# Arduino_Leonardo-REV3b.net
KiCad netlist of a schematic drawn in EAGLE
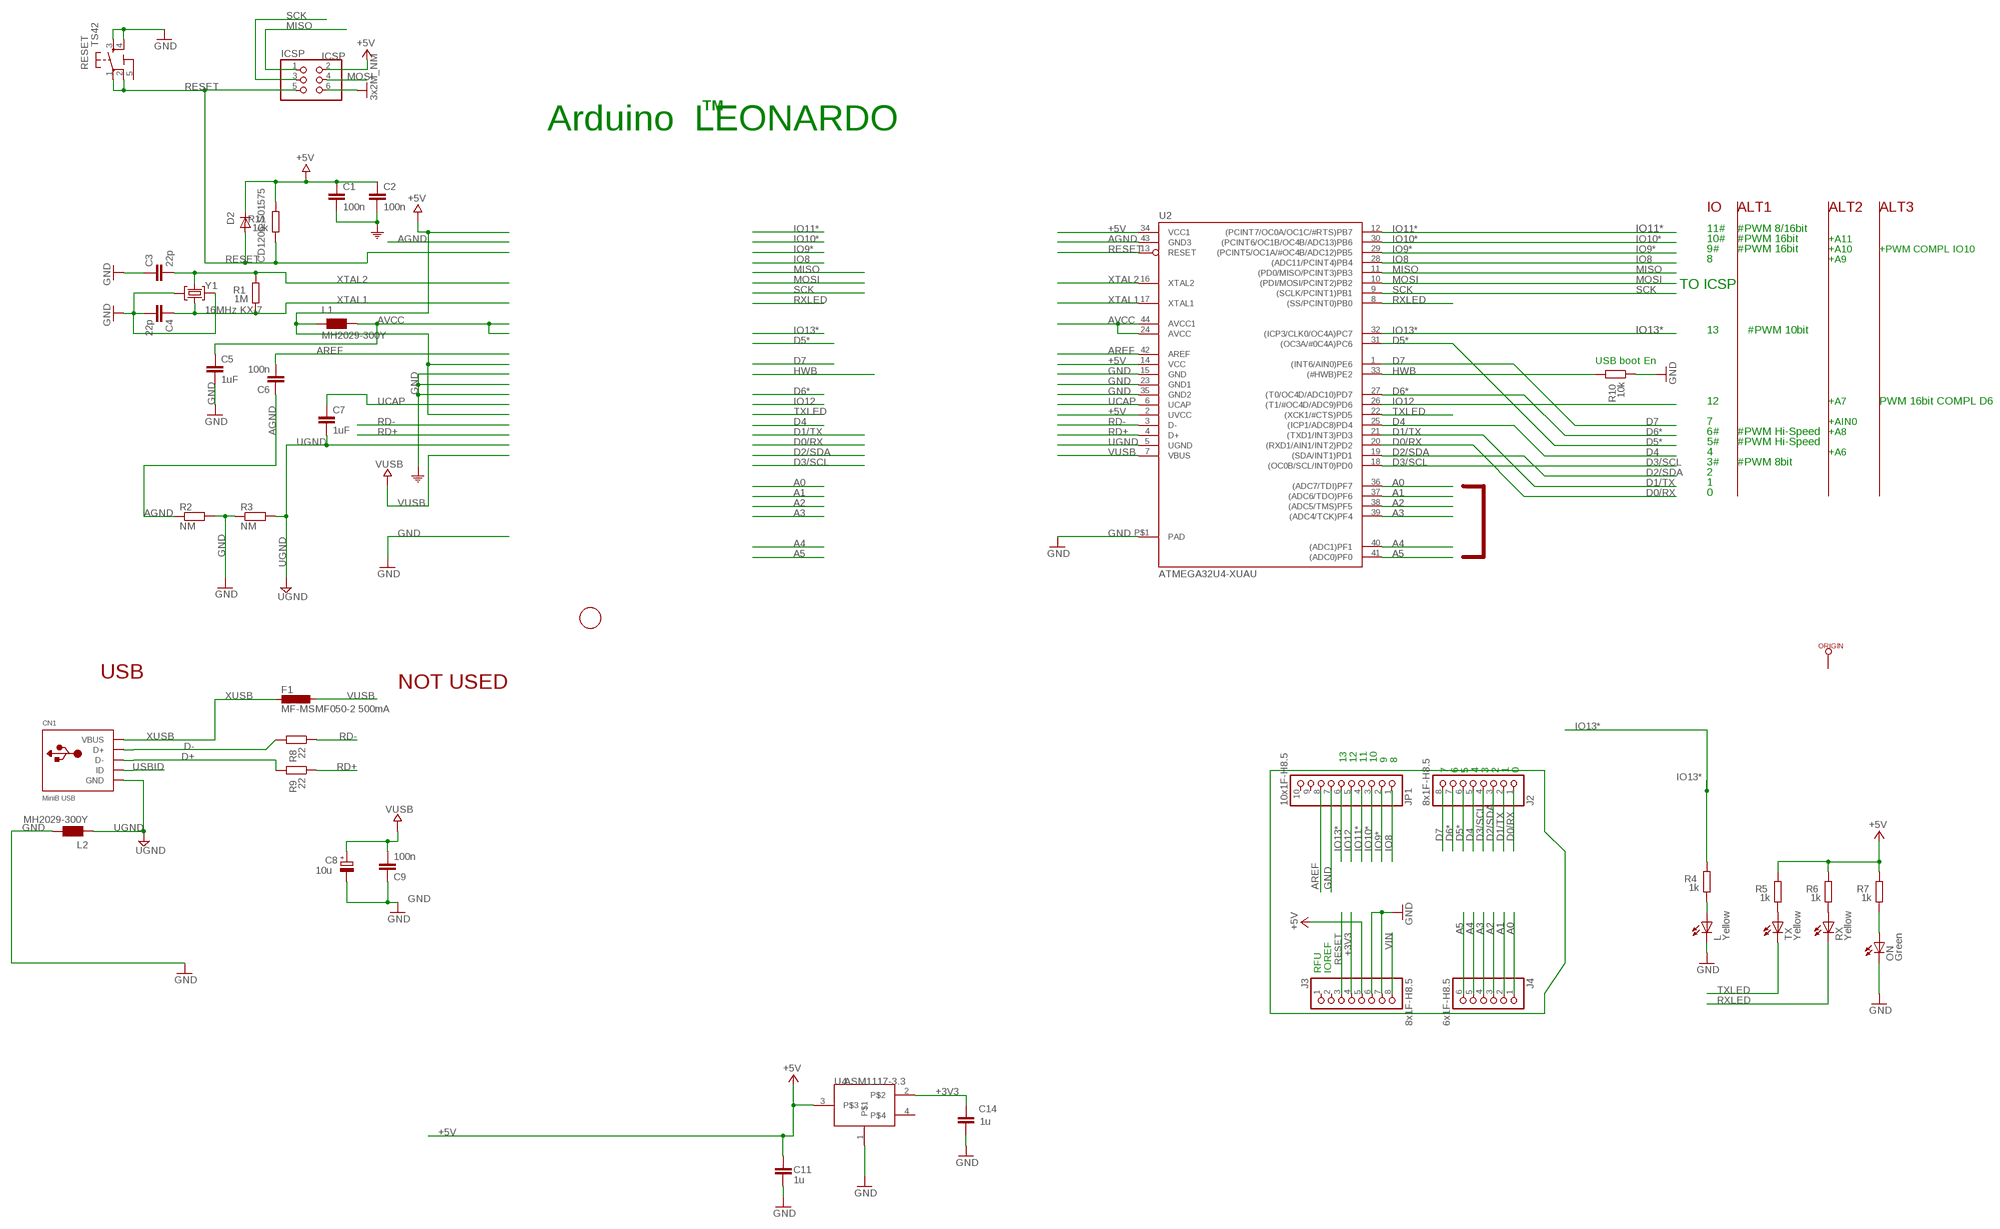
[diagram p0: schematic, sheet 1]

(export (version "E")
  (design (tool "Eeschema 10.0.6"))
  (components
    (comp (ref "C1")
      (value "100n")
      (footprint "eagle-import:C0805")
      (libsource (lib "eagle-import") (part "C-EUC0805"))
    )
    (comp (ref "C2")
      (value "100n")
      (footprint "eagle-import:C0805")
      (libsource (lib "eagle-import") (part "C-EUC0805"))
    )
    (comp (ref "C3")
      (value "22p")
      (footprint "eagle-import:C0805")
      (libsource (lib "eagle-import") (part "C-EUC0805"))
    )
    (comp (ref "C4")
      (value "22p")
      (footprint "eagle-import:C0805")
      (libsource (lib "eagle-import") (part "C-EUC0805"))
    )
    (comp (ref "C5")
      (value "1uF")
      (footprint "eagle-import:C0805")
      (libsource (lib "eagle-import") (part "C-EUC0805"))
    )
    (comp (ref "C6")
      (value "100n")
      (footprint "eagle-import:C0805")
      (libsource (lib "eagle-import") (part "C-EUC0805"))
    )
    (comp (ref "C7")
      (value "1uF")
      (footprint "eagle-import:C0805")
      (libsource (lib "eagle-import") (part "C-EUC0805"))
    )
    (comp (ref "C8")
      (value "10u")
      (footprint "eagle-import:SMC_B")
      (libsource (lib "eagle-import") (part "CPOL-EUSMCB"))
    )
    (comp (ref "C9")
      (value "100n")
      (footprint "eagle-import:C0805")
      (libsource (lib "eagle-import") (part "C-EUC0805"))
    )
    (comp (ref "C11")
      (value "1u")
      (footprint "eagle-import:C0805")
      (libsource (lib "eagle-import") (part "C-EUC0805"))
    )
    (comp (ref "C14")
      (value "1u")
      (footprint "eagle-import:C0805")
      (libsource (lib "eagle-import") (part "C-EUC0805"))
    )
    (comp (ref "CN1")
      (value "MiniB USB")
      (footprint "eagle-import:USB-MINIB")
      (libsource (lib "eagle-import") (part "USBMINIB"))
    )
    (comp (ref "D2")
      (value "CD1206-S01575")
      (footprint "eagle-import:MINIMELF")
      (libsource (lib "eagle-import") (part "DIODE-MINIMELF"))
    )
    (comp (ref "F1")
      (value "MF-MSMF050-2 500mA")
      (footprint "eagle-import:L1812")
      (libsource (lib "eagle-import") (part "L-EUL1812"))
    )
    (comp (ref "FID1")
      (value "FIDUCIALMOUNT")
      (footprint "eagle-import:FIDUCIA-MOUNT")
      (libsource (lib "eagle-import") (part "FIDUCIALMOUNT"))
    )
    (comp (ref "ICSP")
      (value "ICSP")
      (footprint "eagle-import:2X03")
      (libsource (lib "eagle-import") (part "PINHD-2X3"))
    )
    (comp (ref "J2")
      (value "8x1F-H8.5")
      (footprint "eagle-import:1X08")
      (libsource (lib "eagle-import") (part "PINHD-1X8"))
    )
    (comp (ref "J3")
      (value "8x1F-H8.5")
      (footprint "eagle-import:1X08")
      (libsource (lib "eagle-import") (part "PINHD-1X8"))
    )
    (comp (ref "J4")
      (value "6x1F-H8.5")
      (footprint "eagle-import:1X06")
      (libsource (lib "eagle-import") (part "PINHD-1X6"))
    )
    (comp (ref "JP1")
      (value "10x1F-H8.5")
      (footprint "eagle-import:1X10")
      (libsource (lib "eagle-import") (part "PINHD-1X10"))
    )
    (comp (ref "L")
      (value "Yellow")
      (footprint "eagle-import:CHIPLED_0805")
      (libsource (lib "eagle-import") (part "LEDCHIPLED_0805"))
    )
    (comp (ref "L1")
      (value "MH2029-300Y")
      (footprint "eagle-import:0805")
      (libsource (lib "eagle-import") (part "WE-CBF_0805"))
    )
    (comp (ref "L2")
      (value "MH2029-300Y")
      (footprint "eagle-import:0805")
      (libsource (lib "eagle-import") (part "WE-CBF_0805"))
    )
    (comp (ref "ON")
      (value "Green")
      (footprint "eagle-import:CHIPLED_0805")
      (libsource (lib "eagle-import") (part "LEDCHIPLED_0805"))
    )
    (comp (ref "ORIGIN")
      (value "TP_SP")
      (footprint "eagle-import:TP-SP")
      (libsource (lib "eagle-import") (part "TP_SP"))
    )
    (comp (ref "R1")
      (value "1M")
      (footprint "eagle-import:R0805")
      (libsource (lib "eagle-import") (part "R-EU_R0805"))
    )
    (comp (ref "R2")
      (value "NM")
      (footprint "eagle-import:R0805")
      (libsource (lib "eagle-import") (part "R-EU_R0805"))
    )
    (comp (ref "R3")
      (value "NM")
      (footprint "eagle-import:R0805")
      (libsource (lib "eagle-import") (part "R-EU_R0805"))
    )
    (comp (ref "R4")
      (value "1k")
      (footprint "eagle-import:R0805")
      (libsource (lib "eagle-import") (part "R-EU_R0805"))
    )
    (comp (ref "R5")
      (value "1k")
      (footprint "eagle-import:R0805")
      (libsource (lib "eagle-import") (part "R-EU_R0805"))
    )
    (comp (ref "R6")
      (value "1k")
      (footprint "eagle-import:R0805")
      (libsource (lib "eagle-import") (part "R-EU_R0805"))
    )
    (comp (ref "R7")
      (value "1k")
      (footprint "eagle-import:R0805")
      (libsource (lib "eagle-import") (part "R-EU_R0805"))
    )
    (comp (ref "R8")
      (value "22")
      (footprint "eagle-import:R0805")
      (libsource (lib "eagle-import") (part "R-EU_R0805"))
    )
    (comp (ref "R9")
      (value "22")
      (footprint "eagle-import:R0805")
      (libsource (lib "eagle-import") (part "R-EU_R0805"))
    )
    (comp (ref "R10")
      (value "10k")
      (footprint "eagle-import:R0805")
      (libsource (lib "eagle-import") (part "R-EU_R0805"))
    )
    (comp (ref "R11")
      (value "10k")
      (footprint "eagle-import:R0805")
      (libsource (lib "eagle-import") (part "R-EU_R0805"))
    )
    (comp (ref "RESET")
      (value "TS42")
      (footprint "eagle-import:TS42")
      (libsource (lib "eagle-import") (part "TS42"))
    )
    (comp (ref "RX")
      (value "Yellow")
      (footprint "eagle-import:CHIPLED_0805")
      (libsource (lib "eagle-import") (part "LEDCHIPLED_0805"))
    )
    (comp (ref "TX")
      (value "Yellow")
      (footprint "eagle-import:CHIPLED_0805")
      (libsource (lib "eagle-import") (part "LEDCHIPLED_0805"))
    )
    (comp (ref "U2")
      (value "ATMEGA32U4-XUAU")
      (footprint "eagle-import:TQFP44-PAD")
      (libsource (lib "eagle-import") (part "ATMEGA32U4-XUAU"))
    )
    (comp (ref "U4")
      (value "ASM1117-3.3")
      (footprint "eagle-import:SOT223")
      (libsource (lib "eagle-import") (part "ASM1117-3.3"))
    )
    (comp (ref "Y1")
      (value "16MHz KX-7")
      (footprint "eagle-import:CRYSTAL-3.2-2.5")
      (libsource (lib "eagle-import") (part "CRYSTAL-3.2-2.5"))
    )
  )
  (nets
    (net (code "1") (name "+5V") (class "Default")
      (node (ref "C1") (pin "1") (pinfunction "1_1") (pintype "passive"))
      (node (ref "C11") (pin "2") (pinfunction "2_2") (pintype "passive"))
      (node (ref "C2") (pin "1") (pinfunction "1_1") (pintype "passive"))
      (node (ref "D2") (pin "C") (pinfunction "C_C") (pintype "passive"))
      (node (ref "ICSP") (pin "2") (pinfunction "2_2") (pintype "passive"))
      (node (ref "J3") (pin "5") (pinfunction "5_5") (pintype "passive"))
      (node (ref "L1") (pin "1") (pinfunction "1_1") (pintype "passive"))
      (node (ref "R11") (pin "2") (pinfunction "2_2") (pintype "passive"))
      (node (ref "R5") (pin "2") (pinfunction "2_2") (pintype "passive"))
      (node (ref "R6") (pin "2") (pinfunction "2_2") (pintype "passive"))
      (node (ref "R7") (pin "2") (pinfunction "2_2") (pintype "passive"))
      (node (ref "U2") (pin "14") (pinfunction "VCC_14") (pintype "power_in"))
      (node (ref "U2") (pin "2") (pinfunction "UVCC_2") (pintype "power_in"))
      (node (ref "U2") (pin "34") (pinfunction "VCC1_34") (pintype "power_in"))
      (node (ref "U4") (pin "3") (pinfunction "P$3_3") (pintype "bidirectional"))
    )
    (net (code "2") (name "/+3V3") (class "Default")
      (node (ref "C14") (pin "2") (pinfunction "2_2") (pintype "passive"))
      (node (ref "J3") (pin "4") (pinfunction "4_4") (pintype "passive"))
      (node (ref "U4") (pin "2") (pinfunction "P$2_2") (pintype "bidirectional"))
    )
    (net (code "3") (name "/5-GND") (class "Default")
      (node (ref "RESET") (pin "5") (pinfunction "5-GND_5") (pintype "power_in"))
    )
    (net (code "4") (name "/A0") (class "Default")
      (node (ref "J4") (pin "1") (pinfunction "1_1") (pintype "passive"))
      (node (ref "U2") (pin "36") (pinfunction "(ADC7/TDI)PF7_36") (pintype "bidirectional"))
    )
    (net (code "5") (name "/A1") (class "Default")
      (node (ref "J4") (pin "2") (pinfunction "2_2") (pintype "passive"))
      (node (ref "U2") (pin "37") (pinfunction "(ADC6/TDO)PF6_37") (pintype "bidirectional"))
    )
    (net (code "6") (name "/A2") (class "Default")
      (node (ref "J4") (pin "3") (pinfunction "3_3") (pintype "passive"))
      (node (ref "U2") (pin "38") (pinfunction "(ADC5/TMS)PF5_38") (pintype "bidirectional"))
    )
    (net (code "7") (name "/A3") (class "Default")
      (node (ref "J4") (pin "4") (pinfunction "4_4") (pintype "passive"))
      (node (ref "U2") (pin "39") (pinfunction "(ADC4/TCK)PF4_39") (pintype "bidirectional"))
    )
    (net (code "8") (name "/A4") (class "Default")
      (node (ref "J4") (pin "5") (pinfunction "5_5") (pintype "passive"))
      (node (ref "U2") (pin "40") (pinfunction "(ADC1)PF1_40") (pintype "bidirectional"))
    )
    (net (code "9") (name "/A5") (class "Default")
      (node (ref "J4") (pin "6") (pinfunction "6_6") (pintype "passive"))
      (node (ref "U2") (pin "41") (pinfunction "(ADC0)PF0_41") (pintype "bidirectional"))
    )
    (net (code "10") (name "/AGND") (class "Default")
      (node (ref "C6") (pin "1") (pinfunction "1_1") (pintype "passive"))
      (node (ref "R2") (pin "1") (pinfunction "1_1") (pintype "passive"))
      (node (ref "U2") (pin "43") (pinfunction "GND3_43") (pintype "power_in"))
    )
    (net (code "11") (name "/AREF") (class "Default")
      (node (ref "C6") (pin "2") (pinfunction "2_2") (pintype "passive"))
      (node (ref "JP1") (pin "8") (pinfunction "8_8") (pintype "passive"))
      (node (ref "U2") (pin "42") (pinfunction "AREF_42") (pintype "power_in"))
    )
    (net (code "12") (name "/AVCC") (class "Default")
      (node (ref "C5") (pin "1") (pinfunction "1_1") (pintype "passive"))
      (node (ref "L1") (pin "2") (pinfunction "2_2") (pintype "passive"))
      (node (ref "U2") (pin "24") (pinfunction "AVCC_24") (pintype "power_in"))
      (node (ref "U2") (pin "44") (pinfunction "AVCC1_44") (pintype "power_in"))
    )
    (net (code "13") (name "/D+") (class "Default")
      (node (ref "CN1") (pin "D-") (pinfunction "D-_D-") (pintype "bidirectional"))
      (node (ref "R9") (pin "2") (pinfunction "2_2") (pintype "passive"))
    )
    (net (code "14") (name "/D-") (class "Default")
      (node (ref "CN1") (pin "D+") (pinfunction "D+_D+") (pintype "bidirectional"))
      (node (ref "R8") (pin "2") (pinfunction "2_2") (pintype "passive"))
    )
    (net (code "15") (name "/D0{slash}RX") (class "Default")
      (node (ref "J2") (pin "1") (pinfunction "1_1") (pintype "passive"))
      (node (ref "U2") (pin "20") (pinfunction "(RXD1/AIN1/INT2)PD2_20") (pintype "bidirectional"))
    )
    (net (code "16") (name "/D1{slash}TX") (class "Default")
      (node (ref "J2") (pin "2") (pinfunction "2_2") (pintype "passive"))
      (node (ref "U2") (pin "21") (pinfunction "(TXD1/INT3)PD3_21") (pintype "bidirectional"))
    )
    (net (code "17") (name "/D2{slash}SDA") (class "Default")
      (node (ref "J2") (pin "3") (pinfunction "3_3") (pintype "passive"))
      (node (ref "U2") (pin "19") (pinfunction "(SDA/INT1)PD1_19") (pintype "bidirectional"))
    )
    (net (code "18") (name "/D3{slash}SCL") (class "Default")
      (node (ref "J2") (pin "4") (pinfunction "4_4") (pintype "passive"))
      (node (ref "U2") (pin "18") (pinfunction "(OC0B/SCL/INT0)PD0_18") (pintype "bidirectional"))
    )
    (net (code "19") (name "/D4") (class "Default")
      (node (ref "J2") (pin "5") (pinfunction "5_5") (pintype "passive"))
      (node (ref "U2") (pin "25") (pinfunction "(ICP1/ADC8)PD4_25") (pintype "bidirectional"))
    )
    (net (code "20") (name "/D5*") (class "Default")
      (node (ref "J2") (pin "6") (pinfunction "6_6") (pintype "passive"))
      (node (ref "U2") (pin "31") (pinfunction "(OC3A/#0C4A)PC6_31") (pintype "bidirectional"))
    )
    (net (code "21") (name "/D6*") (class "Default")
      (node (ref "J2") (pin "7") (pinfunction "7_7") (pintype "passive"))
      (node (ref "U2") (pin "27") (pinfunction "(T0/OC4D/ADC10)PD7_27") (pintype "bidirectional"))
    )
    (net (code "22") (name "/D7") (class "Default")
      (node (ref "J2") (pin "8") (pinfunction "8_8") (pintype "passive"))
      (node (ref "U2") (pin "1") (pinfunction "(INT6/AIN0)PE6_1") (pintype "bidirectional"))
    )
    (net (code "23") (name "/HWB") (class "Default")
      (node (ref "R10") (pin "2") (pinfunction "2_2") (pintype "passive"))
      (node (ref "U2") (pin "33") (pinfunction "(#HWB)PE2_33") (pintype "bidirectional"))
    )
    (net (code "24") (name "/IO8") (class "Default")
      (node (ref "JP1") (pin "1") (pinfunction "1_1") (pintype "passive"))
      (node (ref "U2") (pin "28") (pinfunction "(ADC11/PCINT4)PB4_28") (pintype "bidirectional"))
    )
    (net (code "25") (name "/IO9*") (class "Default")
      (node (ref "JP1") (pin "2") (pinfunction "2_2") (pintype "passive"))
      (node (ref "U2") (pin "29") (pinfunction "(PCINT5/OC1A/#OC4B/ADC12)PB5_29") (pintype "bidirectional"))
    )
    (net (code "26") (name "/IO10*") (class "Default")
      (node (ref "JP1") (pin "3") (pinfunction "3_3") (pintype "passive"))
      (node (ref "U2") (pin "30") (pinfunction "(PCINT6/OC1B/OC4B/ADC13)PB6_30") (pintype "bidirectional"))
    )
    (net (code "27") (name "/IO11*") (class "Default")
      (node (ref "JP1") (pin "4") (pinfunction "4_4") (pintype "passive"))
      (node (ref "U2") (pin "12") (pinfunction "(PCINT7/OC0A/OC1C/#RTS)PB7_12") (pintype "bidirectional"))
    )
    (net (code "28") (name "/IO12") (class "Default")
      (node (ref "JP1") (pin "5") (pinfunction "5_5") (pintype "passive"))
      (node (ref "U2") (pin "26") (pinfunction "(T1/#OC4D/ADC9)PD6_26") (pintype "bidirectional"))
    )
    (net (code "29") (name "/IO13*") (class "Default")
      (node (ref "JP1") (pin "6") (pinfunction "6_6") (pintype "passive"))
      (node (ref "R4") (pin "2") (pinfunction "2_2") (pintype "passive"))
      (node (ref "U2") (pin "32") (pinfunction "(ICP3/CLK0/OC4A)PC7_32") (pintype "bidirectional"))
    )
    (net (code "30") (name "/MISO") (class "Default")
      (node (ref "ICSP") (pin "1") (pinfunction "1_1") (pintype "passive"))
      (node (ref "U2") (pin "11") (pinfunction "(PD0/MISO/PCINT3)PB3_11") (pintype "bidirectional"))
    )
    (net (code "31") (name "/MOSI") (class "Default")
      (node (ref "ICSP") (pin "4") (pinfunction "4_4") (pintype "passive"))
      (node (ref "U2") (pin "10") (pinfunction "(PDI/MOSI/PCINT2)PB2_10") (pintype "bidirectional"))
    )
    (net (code "32") (name "/RD+") (class "Default")
      (node (ref "R9") (pin "1") (pinfunction "1_1") (pintype "passive"))
      (node (ref "U2") (pin "4") (pinfunction "D+_4") (pintype "bidirectional"))
    )
    (net (code "33") (name "/RD-") (class "Default")
      (node (ref "R8") (pin "1") (pinfunction "1_1") (pintype "passive"))
      (node (ref "U2") (pin "3") (pinfunction "D-_3") (pintype "bidirectional"))
    )
    (net (code "34") (name "/RESET") (class "Default")
      (node (ref "D2") (pin "A") (pinfunction "A_A") (pintype "passive"))
      (node (ref "ICSP") (pin "5") (pinfunction "5_5") (pintype "passive"))
      (node (ref "J3") (pin "3") (pinfunction "3_3") (pintype "passive"))
      (node (ref "R11") (pin "1") (pinfunction "1_1") (pintype "passive"))
      (node (ref "RESET") (pin "1") (pinfunction "1_1") (pintype "passive"))
      (node (ref "RESET") (pin "2") (pinfunction "2_2") (pintype "passive"))
      (node (ref "U2") (pin "13") (pinfunction "RESET_13") (pintype "input"))
    )
    (net (code "35") (name "/RXLED") (class "Default")
      (node (ref "RX") (pin "C") (pinfunction "C_C") (pintype "passive"))
      (node (ref "U2") (pin "8") (pinfunction "(SS/PCINT0)PB0_8") (pintype "bidirectional"))
    )
    (net (code "36") (name "/SCK") (class "Default")
      (node (ref "ICSP") (pin "3") (pinfunction "3_3") (pintype "passive"))
      (node (ref "U2") (pin "9") (pinfunction "(SCLK/PCINT1)PB1_9") (pintype "bidirectional"))
    )
    (net (code "37") (name "/TXLED") (class "Default")
      (node (ref "TX") (pin "C") (pinfunction "C_C") (pintype "passive"))
      (node (ref "U2") (pin "22") (pinfunction "(XCK1/#CTS)PD5_22") (pintype "bidirectional"))
    )
    (net (code "38") (name "/UCAP") (class "Default")
      (node (ref "C7") (pin "1") (pinfunction "1_1") (pintype "passive"))
      (node (ref "U2") (pin "6") (pinfunction "UCAP_6") (pintype "passive"))
    )
    (net (code "39") (name "/USBID") (class "Default")
      (node (ref "CN1") (pin "ID") (pinfunction "ID_ID") (pintype "bidirectional"))
    )
    (net (code "40") (name "/VIN") (class "Default")
      (node (ref "J3") (pin "8") (pinfunction "8_8") (pintype "passive"))
    )
    (net (code "41") (name "/XTAL1") (class "Default")
      (node (ref "C4") (pin "1") (pinfunction "1_1") (pintype "passive"))
      (node (ref "R1") (pin "1") (pinfunction "1_1") (pintype "passive"))
      (node (ref "U2") (pin "17") (pinfunction "XTAL1_17") (pintype "bidirectional"))
      (node (ref "Y1") (pin "1") (pinfunction "C1_1") (pintype "passive"))
    )
    (net (code "42") (name "/XTAL2") (class "Default")
      (node (ref "C3") (pin "2") (pinfunction "2_2") (pintype "passive"))
      (node (ref "R1") (pin "2") (pinfunction "2_2") (pintype "passive"))
      (node (ref "U2") (pin "16") (pinfunction "XTAL2_16") (pintype "bidirectional"))
      (node (ref "Y1") (pin "3") (pinfunction "C2_3") (pintype "passive"))
    )
    (net (code "43") (name "/XUSB") (class "Default")
      (node (ref "CN1") (pin "VBUS") (pinfunction "VBUS_VBUS") (pintype "power_in"))
      (node (ref "F1") (pin "2") (pinfunction "2_2") (pintype "passive"))
    )
    (net (code "44") (name "3x2M_NM") (class "Default")
      (node (ref "C1") (pin "2") (pinfunction "2_2") (pintype "passive"))
      (node (ref "C11") (pin "1") (pinfunction "1_1") (pintype "passive"))
      (node (ref "C14") (pin "1") (pinfunction "1_1") (pintype "passive"))
      (node (ref "C2") (pin "2") (pinfunction "2_2") (pintype "passive"))
      (node (ref "C3") (pin "1") (pinfunction "1_1") (pintype "passive"))
      (node (ref "C4") (pin "2") (pinfunction "2_2") (pintype "passive"))
      (node (ref "C5") (pin "2") (pinfunction "2_2") (pintype "passive"))
      (node (ref "C8") (pin "-") (pinfunction "-_-") (pintype "passive"))
      (node (ref "C9") (pin "1") (pinfunction "1_1") (pintype "passive"))
      (node (ref "ICSP") (pin "6") (pinfunction "6_6") (pintype "passive"))
      (node (ref "J3") (pin "6") (pinfunction "6_6") (pintype "passive"))
      (node (ref "J3") (pin "7") (pinfunction "7_7") (pintype "passive"))
      (node (ref "JP1") (pin "7") (pinfunction "7_7") (pintype "passive"))
      (node (ref "L") (pin "C") (pinfunction "C_C") (pintype "passive"))
      (node (ref "L2") (pin "2") (pinfunction "2_2") (pintype "passive"))
      (node (ref "ON") (pin "C") (pinfunction "C_C") (pintype "passive"))
      (node (ref "R10") (pin "1") (pinfunction "1_1") (pintype "passive"))
      (node (ref "R2") (pin "2") (pinfunction "2_2") (pintype "passive"))
      (node (ref "R3") (pin "1") (pinfunction "1_1") (pintype "passive"))
      (node (ref "RESET") (pin "3") (pinfunction "3_3") (pintype "passive"))
      (node (ref "RESET") (pin "4") (pinfunction "4_4") (pintype "passive"))
      (node (ref "U2") (pin "15") (pinfunction "GND_15") (pintype "power_in"))
      (node (ref "U2") (pin "23") (pinfunction "GND1_23") (pintype "power_in"))
      (node (ref "U2") (pin "35") (pinfunction "GND2_35") (pintype "power_in"))
      (node (ref "U2") (pin "P$1") (pinfunction "PAD_P$1") (pintype "power_in"))
      (node (ref "U4") (pin "1") (pinfunction "P$1_1") (pintype "bidirectional"))
      (node (ref "Y1") (pin "2") (pinfunction "GND_2") (pintype "passive"))
      (node (ref "Y1") (pin "4") (pinfunction "GND_4") (pintype "passive"))
    )
    (net (code "45") (name "Net-(L-PadA)") (class "Default")
      (node (ref "L") (pin "A") (pinfunction "A_A") (pintype "passive"))
      (node (ref "R4") (pin "1") (pinfunction "1_1") (pintype "passive"))
    )
    (net (code "46") (name "Net-(ON-PadA)") (class "Default")
      (node (ref "ON") (pin "A") (pinfunction "A_A") (pintype "passive"))
      (node (ref "R7") (pin "1") (pinfunction "1_1") (pintype "passive"))
    )
    (net (code "47") (name "Net-(R5-Pad1)") (class "Default")
      (node (ref "R5") (pin "1") (pinfunction "1_1") (pintype "passive"))
      (node (ref "TX") (pin "A") (pinfunction "A_A") (pintype "passive"))
    )
    (net (code "48") (name "Net-(R6-Pad1)") (class "Default")
      (node (ref "R6") (pin "1") (pinfunction "1_1") (pintype "passive"))
      (node (ref "RX") (pin "A") (pinfunction "A_A") (pintype "passive"))
    )
    (net (code "49") (name "UGND") (class "Default")
      (node (ref "C7") (pin "2") (pinfunction "2_2") (pintype "passive"))
      (node (ref "CN1") (pin "GND") (pinfunction "GND_GND") (pintype "power_in"))
      (node (ref "L2") (pin "1") (pinfunction "1_1") (pintype "passive"))
      (node (ref "R3") (pin "2") (pinfunction "2_2") (pintype "passive"))
      (node (ref "U2") (pin "5") (pinfunction "UGND_5") (pintype "power_in"))
    )
    (net (code "50") (name "VUSB") (class "Default")
      (node (ref "C8") (pin "+") (pinfunction "+_+") (pintype "passive"))
      (node (ref "C9") (pin "2") (pinfunction "2_2") (pintype "passive"))
      (node (ref "F1") (pin "1") (pinfunction "1_1") (pintype "passive"))
      (node (ref "U2") (pin "7") (pinfunction "VBUS_7") (pintype "input"))
    )
    (net (code "51") (name "unconnected-(J3-Pad1)") (class "Default")
      (node (ref "J3") (pin "1") (pinfunction "1_1") (pintype "passive"))
    )
    (net (code "52") (name "unconnected-(J3-Pad2)") (class "Default")
      (node (ref "J3") (pin "2") (pinfunction "2_2") (pintype "passive"))
    )
    (net (code "53") (name "unconnected-(JP1-Pad9)") (class "Default")
      (node (ref "JP1") (pin "9") (pinfunction "9_9") (pintype "passive"))
    )
    (net (code "54") (name "unconnected-(JP1-Pad10)") (class "Default")
      (node (ref "JP1") (pin "10") (pinfunction "10_10") (pintype "passive"))
    )
    (net (code "55") (name "unconnected-(ORIGIN-TESTP-PadX)") (class "Default")
      (node (ref "ORIGIN") (pin "X") (pinfunction "TESTP_X") (pintype "passive"))
    )
    (net (code "56") (name "unconnected-(U4-P$4-Pad4)") (class "Default")
      (node (ref "U4") (pin "4") (pinfunction "P$4_4") (pintype "bidirectional"))
    )
  )
)
